# Diagrama1.net
KiCad netlist of a schematic drawn in EAGLE
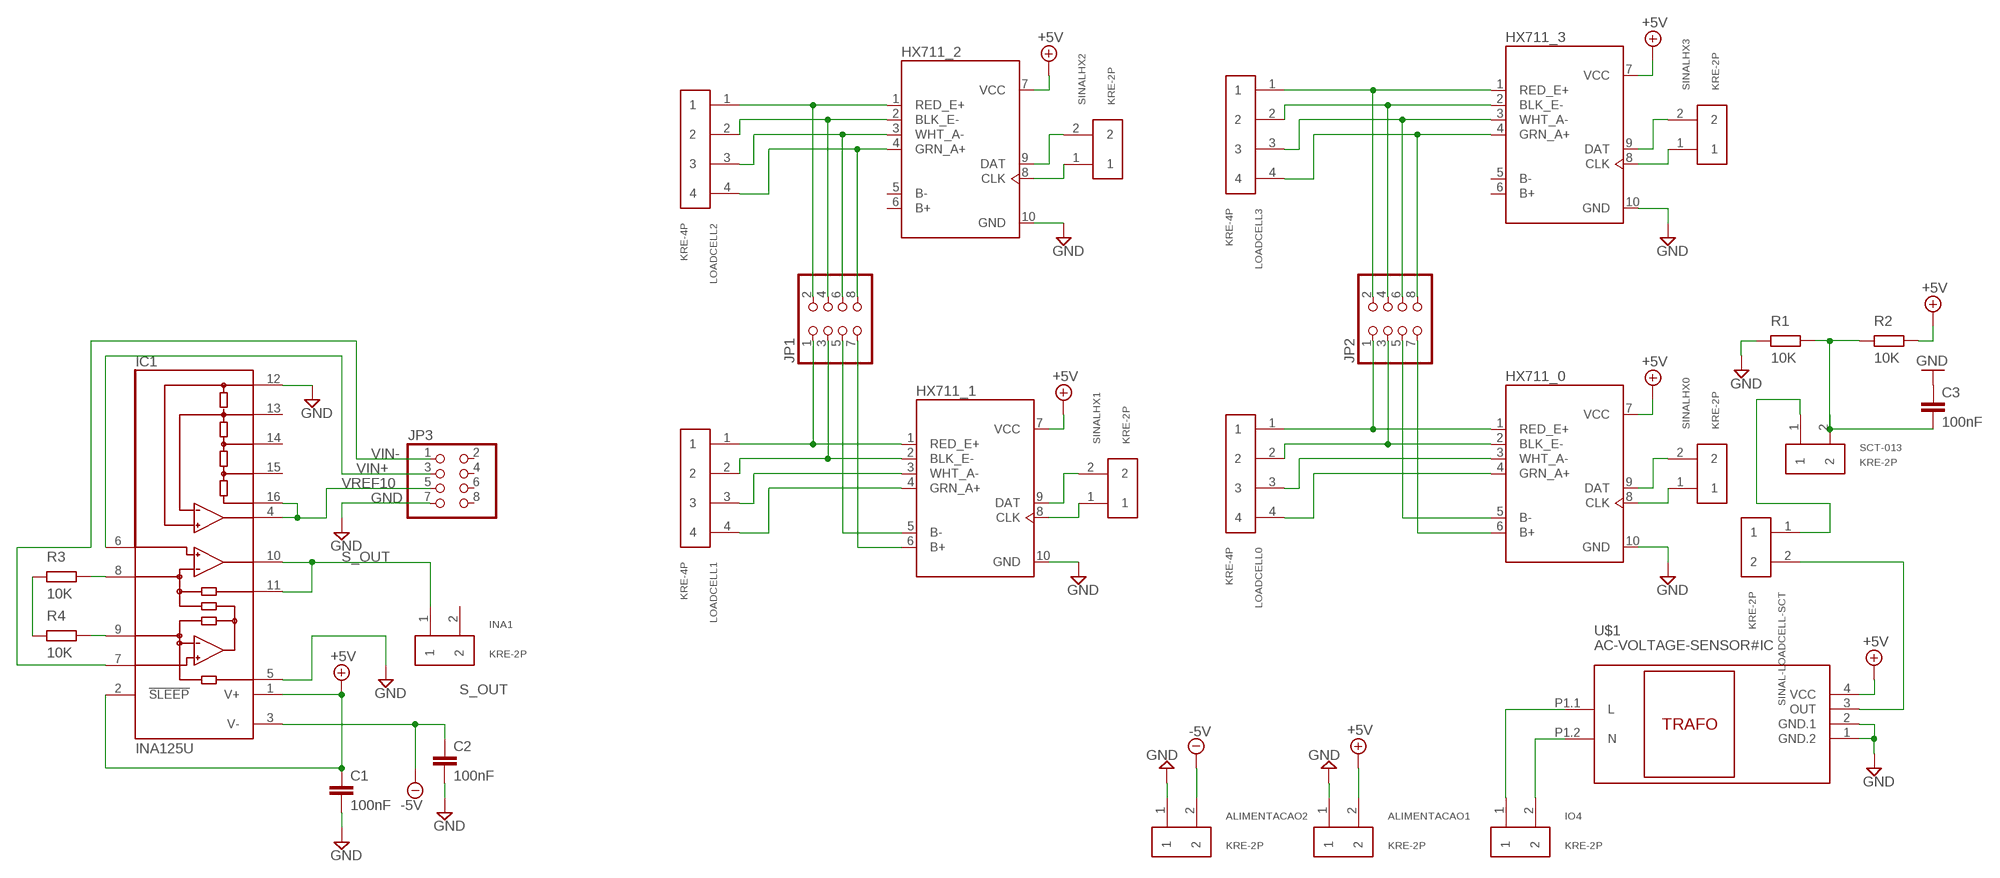
[diagram p0: schematic, sheet 1]

(export (version "E")
  (design (tool "Eeschema 10.0.6"))
  (components
    (comp (ref "ALIMENTACAO1")
      (value "KRE-2P")
      (footprint "eagle-import:KRE-2P")
      (libsource (lib "eagle-import") (part "KRE-2P"))
    )
    (comp (ref "ALIMENTACAO2")
      (value "KRE-2P")
      (footprint "eagle-import:KRE-2P")
      (libsource (lib "eagle-import") (part "KRE-2P"))
    )
    (comp (ref "C1")
      (value "100nF")
      (footprint "eagle-import:C050-025X075")
      (libsource (lib "eagle-import") (part "C-EU050-025X075"))
    )
    (comp (ref "C2")
      (value "100nF")
      (footprint "eagle-import:C050-025X075")
      (libsource (lib "eagle-import") (part "C-EU050-025X075"))
    )
    (comp (ref "C3")
      (value "100nF")
      (footprint "eagle-import:C050-025X075")
      (libsource (lib "eagle-import") (part "C-EU050-025X075"))
    )
    (comp (ref "HX711_0")
      (value "HX711MODULO")
      (footprint "eagle-import:HX711MODULO")
      (fields (field (name "MF") "SparkFun") (field (name "MP") "SEN-13879"))
      (libsource (lib "eagle-import") (part "HX711MODULO"))
    )
    (comp (ref "HX711_1")
      (value "HX711MODULO")
      (footprint "eagle-import:HX711MODULO")
      (fields (field (name "MF") "SparkFun") (field (name "MP") "SEN-13879"))
      (libsource (lib "eagle-import") (part "HX711MODULO"))
    )
    (comp (ref "HX711_2")
      (value "HX711MODULO")
      (footprint "eagle-import:HX711MODULO")
      (fields (field (name "MF") "SparkFun") (field (name "MP") "SEN-13879"))
      (libsource (lib "eagle-import") (part "HX711MODULO"))
    )
    (comp (ref "HX711_3")
      (value "HX711MODULO")
      (footprint "eagle-import:HX711MODULO")
      (fields (field (name "MF") "SparkFun") (field (name "MP") "SEN-13879"))
      (libsource (lib "eagle-import") (part "HX711MODULO"))
    )
    (comp (ref "IC1")
      (value "INA125U")
      (footprint "eagle-import:SO16-1")
      (libsource (lib "eagle-import") (part "INA125U"))
    )
    (comp (ref "INA1")
      (value "KRE-2P")
      (footprint "eagle-import:KRE-2P")
      (libsource (lib "eagle-import") (part "KRE-2P"))
    )
    (comp (ref "IO4")
      (value "KRE-2P")
      (footprint "eagle-import:KRE-2P")
      (libsource (lib "eagle-import") (part "KRE-2P"))
    )
    (comp (ref "JP1")
      (value "PINHD-2X4")
      (footprint "eagle-import:2X04")
      (libsource (lib "eagle-import") (part "PINHD-2X4"))
    )
    (comp (ref "JP2")
      (value "PINHD-2X4")
      (footprint "eagle-import:2X04")
      (libsource (lib "eagle-import") (part "PINHD-2X4"))
    )
    (comp (ref "JP3")
      (value "PINHD-2X4")
      (footprint "eagle-import:2X04")
      (libsource (lib "eagle-import") (part "PINHD-2X4"))
    )
    (comp (ref "LOADCELL0")
      (value "KRE-4P")
      (footprint "eagle-import:KRE-4P")
      (libsource (lib "eagle-import") (part "KRE-4P"))
    )
    (comp (ref "LOADCELL1")
      (value "KRE-4P")
      (footprint "eagle-import:KRE-4P")
      (libsource (lib "eagle-import") (part "KRE-4P"))
    )
    (comp (ref "LOADCELL2")
      (value "KRE-4P")
      (footprint "eagle-import:KRE-4P")
      (libsource (lib "eagle-import") (part "KRE-4P"))
    )
    (comp (ref "LOADCELL3")
      (value "KRE-4P")
      (footprint "eagle-import:KRE-4P")
      (libsource (lib "eagle-import") (part "KRE-4P"))
    )
    (comp (ref "R1")
      (value "10K")
      (footprint "eagle-import:1_4W-0.41K")
      (libsource (lib "eagle-import") (part "1K1/4RESISTOR"))
    )
    (comp (ref "R2")
      (value "10K")
      (footprint "eagle-import:1_4W-0.41K")
      (libsource (lib "eagle-import") (part "1K1/4RESISTOR"))
    )
    (comp (ref "R3")
      (value "10K")
      (footprint "eagle-import:1_4W-0.41K")
      (libsource (lib "eagle-import") (part "1K1/4RESISTOR"))
    )
    (comp (ref "R4")
      (value "10K")
      (footprint "eagle-import:1_4W-0.41K")
      (libsource (lib "eagle-import") (part "1K1/4RESISTOR"))
    )
    (comp (ref "SCT-013")
      (value "KRE-2P")
      (footprint "eagle-import:KRE-2P")
      (libsource (lib "eagle-import") (part "KRE-2P"))
    )
    (comp (ref "SINAL-LOADCELL-SCT")
      (value "KRE-2P")
      (footprint "eagle-import:KRE-2P")
      (libsource (lib "eagle-import") (part "KRE-2P"))
    )
    (comp (ref "SINALHX0")
      (value "KRE-2P")
      (footprint "eagle-import:KRE-2P")
      (libsource (lib "eagle-import") (part "KRE-2P"))
    )
    (comp (ref "SINALHX1")
      (value "KRE-2P")
      (footprint "eagle-import:KRE-2P")
      (libsource (lib "eagle-import") (part "KRE-2P"))
    )
    (comp (ref "SINALHX2")
      (value "KRE-2P")
      (footprint "eagle-import:KRE-2P")
      (libsource (lib "eagle-import") (part "KRE-2P"))
    )
    (comp (ref "SINALHX3")
      (value "KRE-2P")
      (footprint "eagle-import:KRE-2P")
      (libsource (lib "eagle-import") (part "KRE-2P"))
    )
    (comp (ref "U$1")
      (value "AC-VOLTAGE-SENSOR#IC")
      (footprint "eagle-import:AC-VOLTAGE-SENSOR#IC")
      (libsource (lib "eagle-import") (part "AC-VOLTAGE-SENSOR#IC"))
    )
  )
  (nets
    (net (code "1") (name "+5V") (class "Default")
      (node (ref "ALIMENTACAO1") (pin "2") (pinfunction "2_2") (pintype "bidirectional"))
      (node (ref "C1") (pin "1") (pinfunction "1_1") (pintype "passive"))
      (node (ref "HX711_0") (pin "7") (pinfunction "VCC_7") (pintype "power_in"))
      (node (ref "HX711_1") (pin "7") (pinfunction "VCC_7") (pintype "power_in"))
      (node (ref "HX711_2") (pin "7") (pinfunction "VCC_7") (pintype "power_in"))
      (node (ref "HX711_3") (pin "7") (pinfunction "VCC_7") (pintype "power_in"))
      (node (ref "IC1") (pin "1") (pinfunction "V+_1") (pintype "power_in"))
      (node (ref "IC1") (pin "2") (pinfunction "~{SLEEP}_2") (pintype "input"))
      (node (ref "R2") (pin "2") (pinfunction "2_2") (pintype "passive"))
      (node (ref "U$1") (pin "4") (pinfunction "VCC_4") (pintype "power_in"))
    )
    (net (code "2") (name "-5V") (class "Default")
      (node (ref "ALIMENTACAO2") (pin "2") (pinfunction "2_2") (pintype "bidirectional"))
      (node (ref "C2") (pin "1") (pinfunction "1_1") (pintype "passive"))
      (node (ref "IC1") (pin "3") (pinfunction "V-_3") (pintype "power_in"))
    )
    (net (code "3") (name "/S_OUT") (class "Default")
      (node (ref "IC1") (pin "10") (pinfunction "OUT_10") (pintype "output"))
      (node (ref "IC1") (pin "11") (pinfunction "SENSE_11") (pintype "passive"))
      (node (ref "INA1") (pin "1") (pinfunction "1_1") (pintype "bidirectional"))
    )
    (net (code "4") (name "/VIN+") (class "Default")
      (node (ref "IC1") (pin "6") (pinfunction "+IN_6") (pintype "input"))
      (node (ref "JP3") (pin "3") (pinfunction "3_3") (pintype "passive"))
    )
    (net (code "5") (name "/VIN-") (class "Default")
      (node (ref "IC1") (pin "7") (pinfunction "-IN_7") (pintype "input"))
      (node (ref "JP3") (pin "1") (pinfunction "1_1") (pintype "passive"))
    )
    (net (code "6") (name "/VREF10") (class "Default")
      (node (ref "IC1") (pin "16") (pinfunction "REF10_16") (pintype "output"))
      (node (ref "IC1") (pin "4") (pinfunction "REFOUT_4") (pintype "output"))
      (node (ref "JP3") (pin "5") (pinfunction "5_5") (pintype "passive"))
    )
    (net (code "7") (name "GND") (class "Default")
      (node (ref "ALIMENTACAO1") (pin "1") (pinfunction "1_1") (pintype "bidirectional"))
      (node (ref "ALIMENTACAO2") (pin "1") (pinfunction "1_1") (pintype "bidirectional"))
      (node (ref "C1") (pin "2") (pinfunction "2_2") (pintype "passive"))
      (node (ref "C2") (pin "2") (pinfunction "2_2") (pintype "passive"))
      (node (ref "C3") (pin "1") (pinfunction "1_1") (pintype "passive"))
      (node (ref "HX711_0") (pin "10") (pinfunction "GND_10") (pintype "power_in"))
      (node (ref "HX711_1") (pin "10") (pinfunction "GND_10") (pintype "power_in"))
      (node (ref "HX711_2") (pin "10") (pinfunction "GND_10") (pintype "power_in"))
      (node (ref "HX711_3") (pin "10") (pinfunction "GND_10") (pintype "power_in"))
      (node (ref "IC1") (pin "12") (pinfunction "REFCOM_12") (pintype "passive"))
      (node (ref "IC1") (pin "5") (pinfunction "REF_5") (pintype "passive"))
      (node (ref "JP3") (pin "7") (pinfunction "7_7") (pintype "passive"))
      (node (ref "R1") (pin "1") (pinfunction "1_1") (pintype "passive"))
      (node (ref "U$1") (pin "1") (pinfunction "GND.2_1") (pintype "power_in"))
      (node (ref "U$1") (pin "2") (pinfunction "GND.1_2") (pintype "power_in"))
    )
    (net (code "8") (name "Net-(C3-Pad2)") (class "Default")
      (node (ref "C3") (pin "2") (pinfunction "2_2") (pintype "passive"))
      (node (ref "R1") (pin "2") (pinfunction "2_2") (pintype "passive"))
      (node (ref "R2") (pin "1") (pinfunction "1_1") (pintype "passive"))
      (node (ref "SCT-013") (pin "2") (pinfunction "2_2") (pintype "bidirectional"))
    )
    (net (code "9") (name "Net-(HX711_0-B+)") (class "Default")
      (node (ref "HX711_0") (pin "6") (pinfunction "B+_6") (pintype "input"))
      (node (ref "JP2") (pin "7") (pinfunction "7_7") (pintype "passive"))
    )
    (net (code "10") (name "Net-(HX711_0-B-)") (class "Default")
      (node (ref "HX711_0") (pin "5") (pinfunction "B-_5") (pintype "input"))
      (node (ref "JP2") (pin "5") (pinfunction "5_5") (pintype "passive"))
    )
    (net (code "11") (name "Net-(HX711_0-BLK_E-)") (class "Default")
      (node (ref "HX711_0") (pin "2") (pinfunction "BLK_E-_2") (pintype "bidirectional"))
      (node (ref "JP2") (pin "3") (pinfunction "3_3") (pintype "passive"))
      (node (ref "LOADCELL0") (pin "2") (pinfunction "2_2") (pintype "bidirectional"))
    )
    (net (code "12") (name "Net-(HX711_0-CLK)") (class "Default")
      (node (ref "HX711_0") (pin "8") (pinfunction "CLK_8") (pintype "input"))
      (node (ref "SINALHX0") (pin "1") (pinfunction "1_1") (pintype "bidirectional"))
    )
    (net (code "13") (name "Net-(HX711_0-DAT)") (class "Default")
      (node (ref "HX711_0") (pin "9") (pinfunction "DAT_9") (pintype "output"))
      (node (ref "SINALHX0") (pin "2") (pinfunction "2_2") (pintype "bidirectional"))
    )
    (net (code "14") (name "Net-(HX711_0-GRN_A+)") (class "Default")
      (node (ref "HX711_0") (pin "4") (pinfunction "GRN_A+_4") (pintype "input"))
      (node (ref "LOADCELL0") (pin "4") (pinfunction "4_4") (pintype "bidirectional"))
    )
    (net (code "15") (name "Net-(HX711_0-RED_E+)") (class "Default")
      (node (ref "HX711_0") (pin "1") (pinfunction "RED_E+_1") (pintype "bidirectional"))
      (node (ref "JP2") (pin "1") (pinfunction "1_1") (pintype "passive"))
      (node (ref "LOADCELL0") (pin "1") (pinfunction "1_1") (pintype "bidirectional"))
    )
    (net (code "16") (name "Net-(HX711_0-WHT_A-)") (class "Default")
      (node (ref "HX711_0") (pin "3") (pinfunction "WHT_A-_3") (pintype "input"))
      (node (ref "LOADCELL0") (pin "3") (pinfunction "3_3") (pintype "bidirectional"))
    )
    (net (code "17") (name "Net-(HX711_1-B+)") (class "Default")
      (node (ref "HX711_1") (pin "6") (pinfunction "B+_6") (pintype "input"))
      (node (ref "JP1") (pin "7") (pinfunction "7_7") (pintype "passive"))
    )
    (net (code "18") (name "Net-(HX711_1-B-)") (class "Default")
      (node (ref "HX711_1") (pin "5") (pinfunction "B-_5") (pintype "input"))
      (node (ref "JP1") (pin "5") (pinfunction "5_5") (pintype "passive"))
    )
    (net (code "19") (name "Net-(HX711_1-BLK_E-)") (class "Default")
      (node (ref "HX711_1") (pin "2") (pinfunction "BLK_E-_2") (pintype "bidirectional"))
      (node (ref "JP1") (pin "3") (pinfunction "3_3") (pintype "passive"))
      (node (ref "LOADCELL1") (pin "2") (pinfunction "2_2") (pintype "bidirectional"))
    )
    (net (code "20") (name "Net-(HX711_1-CLK)") (class "Default")
      (node (ref "HX711_1") (pin "8") (pinfunction "CLK_8") (pintype "input"))
      (node (ref "SINALHX1") (pin "1") (pinfunction "1_1") (pintype "bidirectional"))
    )
    (net (code "21") (name "Net-(HX711_1-DAT)") (class "Default")
      (node (ref "HX711_1") (pin "9") (pinfunction "DAT_9") (pintype "output"))
      (node (ref "SINALHX1") (pin "2") (pinfunction "2_2") (pintype "bidirectional"))
    )
    (net (code "22") (name "Net-(HX711_1-GRN_A+)") (class "Default")
      (node (ref "HX711_1") (pin "4") (pinfunction "GRN_A+_4") (pintype "input"))
      (node (ref "LOADCELL1") (pin "4") (pinfunction "4_4") (pintype "bidirectional"))
    )
    (net (code "23") (name "Net-(HX711_1-RED_E+)") (class "Default")
      (node (ref "HX711_1") (pin "1") (pinfunction "RED_E+_1") (pintype "bidirectional"))
      (node (ref "JP1") (pin "1") (pinfunction "1_1") (pintype "passive"))
      (node (ref "LOADCELL1") (pin "1") (pinfunction "1_1") (pintype "bidirectional"))
    )
    (net (code "24") (name "Net-(HX711_1-WHT_A-)") (class "Default")
      (node (ref "HX711_1") (pin "3") (pinfunction "WHT_A-_3") (pintype "input"))
      (node (ref "LOADCELL1") (pin "3") (pinfunction "3_3") (pintype "bidirectional"))
    )
    (net (code "25") (name "Net-(HX711_2-BLK_E-)") (class "Default")
      (node (ref "HX711_2") (pin "2") (pinfunction "BLK_E-_2") (pintype "bidirectional"))
      (node (ref "JP1") (pin "4") (pinfunction "4_4") (pintype "passive"))
      (node (ref "LOADCELL2") (pin "2") (pinfunction "2_2") (pintype "bidirectional"))
    )
    (net (code "26") (name "Net-(HX711_2-CLK)") (class "Default")
      (node (ref "HX711_2") (pin "8") (pinfunction "CLK_8") (pintype "input"))
      (node (ref "SINALHX2") (pin "1") (pinfunction "1_1") (pintype "bidirectional"))
    )
    (net (code "27") (name "Net-(HX711_2-DAT)") (class "Default")
      (node (ref "HX711_2") (pin "9") (pinfunction "DAT_9") (pintype "output"))
      (node (ref "SINALHX2") (pin "2") (pinfunction "2_2") (pintype "bidirectional"))
    )
    (net (code "28") (name "Net-(HX711_2-GRN_A+)") (class "Default")
      (node (ref "HX711_2") (pin "4") (pinfunction "GRN_A+_4") (pintype "input"))
      (node (ref "JP1") (pin "8") (pinfunction "8_8") (pintype "passive"))
      (node (ref "LOADCELL2") (pin "4") (pinfunction "4_4") (pintype "bidirectional"))
    )
    (net (code "29") (name "Net-(HX711_2-RED_E+)") (class "Default")
      (node (ref "HX711_2") (pin "1") (pinfunction "RED_E+_1") (pintype "bidirectional"))
      (node (ref "JP1") (pin "2") (pinfunction "2_2") (pintype "passive"))
      (node (ref "LOADCELL2") (pin "1") (pinfunction "1_1") (pintype "bidirectional"))
    )
    (net (code "30") (name "Net-(HX711_2-WHT_A-)") (class "Default")
      (node (ref "HX711_2") (pin "3") (pinfunction "WHT_A-_3") (pintype "input"))
      (node (ref "JP1") (pin "6") (pinfunction "6_6") (pintype "passive"))
      (node (ref "LOADCELL2") (pin "3") (pinfunction "3_3") (pintype "bidirectional"))
    )
    (net (code "31") (name "Net-(HX711_3-BLK_E-)") (class "Default")
      (node (ref "HX711_3") (pin "2") (pinfunction "BLK_E-_2") (pintype "bidirectional"))
      (node (ref "JP2") (pin "4") (pinfunction "4_4") (pintype "passive"))
      (node (ref "LOADCELL3") (pin "2") (pinfunction "2_2") (pintype "bidirectional"))
    )
    (net (code "32") (name "Net-(HX711_3-CLK)") (class "Default")
      (node (ref "HX711_3") (pin "8") (pinfunction "CLK_8") (pintype "input"))
      (node (ref "SINALHX3") (pin "1") (pinfunction "1_1") (pintype "bidirectional"))
    )
    (net (code "33") (name "Net-(HX711_3-DAT)") (class "Default")
      (node (ref "HX711_3") (pin "9") (pinfunction "DAT_9") (pintype "output"))
      (node (ref "SINALHX3") (pin "2") (pinfunction "2_2") (pintype "bidirectional"))
    )
    (net (code "34") (name "Net-(HX711_3-GRN_A+)") (class "Default")
      (node (ref "HX711_3") (pin "4") (pinfunction "GRN_A+_4") (pintype "input"))
      (node (ref "JP2") (pin "8") (pinfunction "8_8") (pintype "passive"))
      (node (ref "LOADCELL3") (pin "4") (pinfunction "4_4") (pintype "bidirectional"))
    )
    (net (code "35") (name "Net-(HX711_3-RED_E+)") (class "Default")
      (node (ref "HX711_3") (pin "1") (pinfunction "RED_E+_1") (pintype "bidirectional"))
      (node (ref "JP2") (pin "2") (pinfunction "2_2") (pintype "passive"))
      (node (ref "LOADCELL3") (pin "1") (pinfunction "1_1") (pintype "bidirectional"))
    )
    (net (code "36") (name "Net-(HX711_3-WHT_A-)") (class "Default")
      (node (ref "HX711_3") (pin "3") (pinfunction "WHT_A-_3") (pintype "input"))
      (node (ref "JP2") (pin "6") (pinfunction "6_6") (pintype "passive"))
      (node (ref "LOADCELL3") (pin "3") (pinfunction "3_3") (pintype "bidirectional"))
    )
    (net (code "37") (name "Net-(IC1-RG-Pad8)") (class "Default")
      (node (ref "IC1") (pin "8") (pinfunction "RG_8") (pintype "passive"))
      (node (ref "R3") (pin "2") (pinfunction "2_2") (pintype "passive"))
    )
    (net (code "38") (name "Net-(IC1-RG-Pad9)") (class "Default")
      (node (ref "IC1") (pin "9") (pinfunction "RG_9") (pintype "passive"))
      (node (ref "R4") (pin "2") (pinfunction "2_2") (pintype "passive"))
    )
    (net (code "39") (name "Net-(R3-Pad1)") (class "Default")
      (node (ref "R3") (pin "1") (pinfunction "1_1") (pintype "passive"))
      (node (ref "R4") (pin "1") (pinfunction "1_1") (pintype "passive"))
    )
    (net (code "40") (name "Net-(SCT-013-Pad1)") (class "Default")
      (node (ref "SCT-013") (pin "1") (pinfunction "1_1") (pintype "bidirectional"))
      (node (ref "SINAL-LOADCELL-SCT") (pin "1") (pinfunction "1_1") (pintype "bidirectional"))
    )
    (net (code "41") (name "Net-(U$1-L)") (class "Default")
      (node (ref "IO4") (pin "1") (pinfunction "1_1") (pintype "bidirectional"))
      (node (ref "U$1") (pin "P1.1") (pinfunction "L_P1.1") (pintype "passive"))
    )
    (net (code "42") (name "Net-(U$1-N)") (class "Default")
      (node (ref "IO4") (pin "2") (pinfunction "2_2") (pintype "bidirectional"))
      (node (ref "U$1") (pin "P1.2") (pinfunction "N_P1.2") (pintype "passive"))
    )
    (net (code "43") (name "Net-(U$1-OUT)") (class "Default")
      (node (ref "SINAL-LOADCELL-SCT") (pin "2") (pinfunction "2_2") (pintype "bidirectional"))
      (node (ref "U$1") (pin "3") (pinfunction "OUT_3") (pintype "output"))
    )
    (net (code "44") (name "unconnected-(HX711_2-B+-Pad6)") (class "Default")
      (node (ref "HX711_2") (pin "6") (pinfunction "B+_6") (pintype "input"))
    )
    (net (code "45") (name "unconnected-(HX711_2-B--Pad5)") (class "Default")
      (node (ref "HX711_2") (pin "5") (pinfunction "B-_5") (pintype "input"))
    )
    (net (code "46") (name "unconnected-(HX711_3-B+-Pad6)") (class "Default")
      (node (ref "HX711_3") (pin "6") (pinfunction "B+_6") (pintype "input"))
    )
    (net (code "47") (name "unconnected-(HX711_3-B--Pad5)") (class "Default")
      (node (ref "HX711_3") (pin "5") (pinfunction "B-_5") (pintype "input"))
    )
    (net (code "48") (name "unconnected-(IC1-REF2.5-Pad14)") (class "Default")
      (node (ref "IC1") (pin "14") (pinfunction "REF2.5_14") (pintype "output"))
    )
    (net (code "49") (name "unconnected-(IC1-REF5-Pad15)") (class "Default")
      (node (ref "IC1") (pin "15") (pinfunction "REF5_15") (pintype "output"))
    )
    (net (code "50") (name "unconnected-(IC1-REFBG-Pad13)") (class "Default")
      (node (ref "IC1") (pin "13") (pinfunction "REFBG_13") (pintype "output"))
    )
    (net (code "51") (name "unconnected-(INA1-Pad2)") (class "Default")
      (node (ref "INA1") (pin "2") (pinfunction "2_2") (pintype "bidirectional"))
    )
    (net (code "52") (name "unconnected-(JP3-Pad2)") (class "Default")
      (node (ref "JP3") (pin "2") (pinfunction "2_2") (pintype "passive"))
    )
    (net (code "53") (name "unconnected-(JP3-Pad4)") (class "Default")
      (node (ref "JP3") (pin "4") (pinfunction "4_4") (pintype "passive"))
    )
    (net (code "54") (name "unconnected-(JP3-Pad6)") (class "Default")
      (node (ref "JP3") (pin "6") (pinfunction "6_6") (pintype "passive"))
    )
    (net (code "55") (name "unconnected-(JP3-Pad8)") (class "Default")
      (node (ref "JP3") (pin "8") (pinfunction "8_8") (pintype "passive"))
    )
  )
)
